# Proximity_Sensor.net
KiCad netlist of a schematic drawn in EAGLE
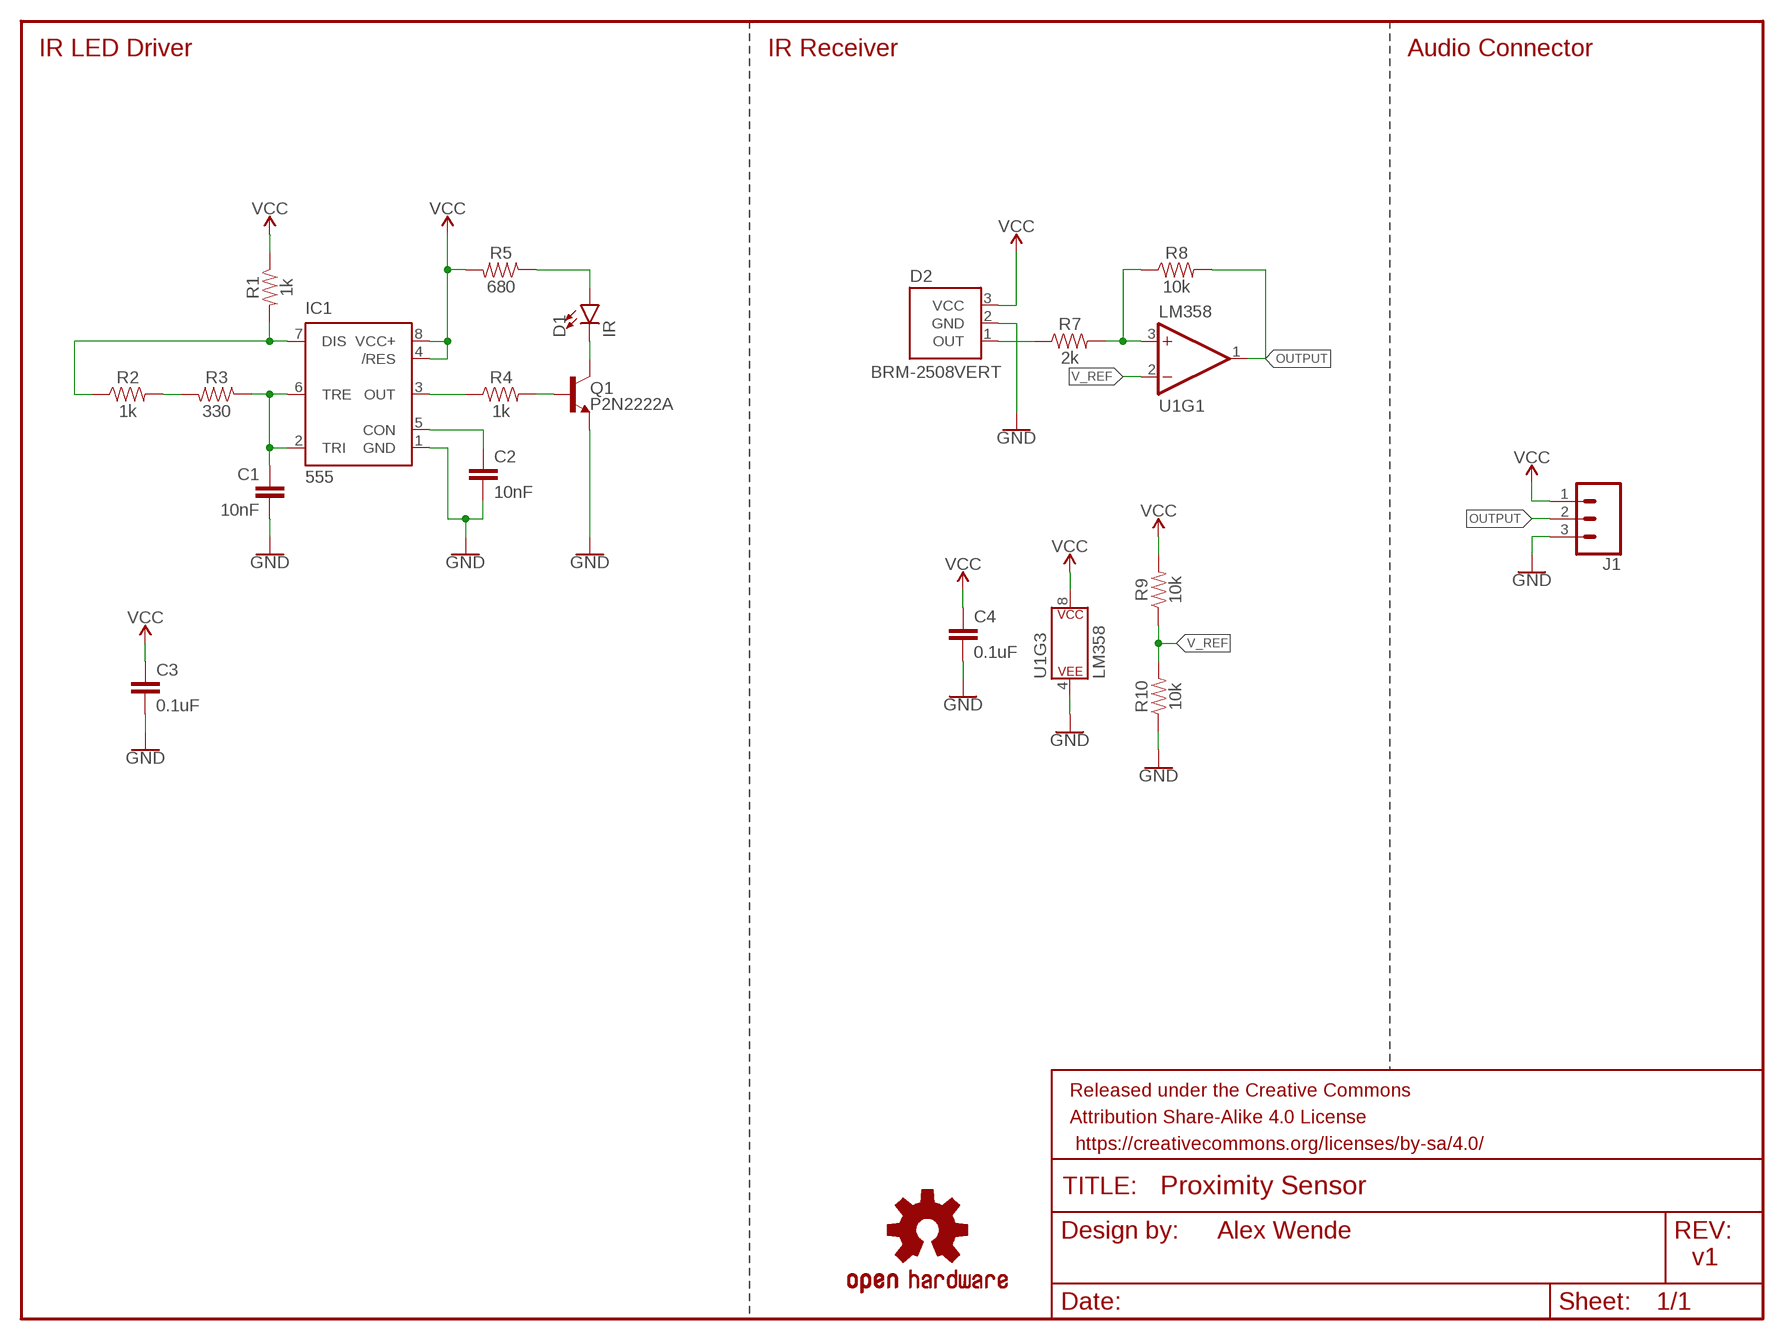
[diagram p0: schematic, sheet 1]

(export (version "E")
  (design (tool "Eeschema 10.0.6"))
  (components
    (comp (ref "C1")
      (value "10nF")
      (footprint "eagle-import:CAP-PTH-10MM")
      (libsource (lib "eagle-import") (part "10NF-PTH-10MM-10000V-1-%"))
    )
    (comp (ref "C2")
      (value "10nF")
      (footprint "eagle-import:CAP-PTH-10MM")
      (libsource (lib "eagle-import") (part "10NF-PTH-10MM-10000V-1-%"))
    )
    (comp (ref "C3")
      (value "0.1uF")
      (footprint "eagle-import:CAP-PTH-SMALL-KIT")
      (libsource (lib "eagle-import") (part "0.1UF-KIT-EZ-50V-20%"))
    )
    (comp (ref "C4")
      (value "0.1uF")
      (footprint "eagle-import:CAP-PTH-SMALL-KIT")
      (libsource (lib "eagle-import") (part "0.1UF-KIT-EZ-50V-20%"))
    )
    (comp (ref "D1")
      (value "IR")
      (footprint "eagle-import:LED_5MM-KIT")
      (libsource (lib "eagle-import") (part "LED5MM-KIT"))
    )
    (comp (ref "D2")
      (value "BRM-2508VERT")
      (footprint "eagle-import:BRM-2508_VERT")
      (libsource (lib "eagle-import") (part "BRM-2508VERT"))
    )
    (comp (ref "FRAME1")
      (value "FRAME-LETTERNO_PACKAGE")
      (footprint "eagle-import:DUMMY")
      (fields (field (name "DESIGNER") "Nobody"))
      (libsource (lib "eagle-import") (part "FRAME-LETTERNO_PACKAGE"))
    )
    (comp (ref "IC1")
      (value "555")
      (footprint "eagle-import:DIP08-KIT")
      (libsource (lib "eagle-import") (part "555KIT"))
    )
    (comp (ref "J1")
      (value "CONN_03LONGPADS")
      (footprint "eagle-import:1X03_LONGPADS")
      (libsource (lib "eagle-import") (part "CONN_03LONGPADS"))
    )
    (comp (ref "LOGO1")
      (value "OSHW-LOGOM")
      (footprint "eagle-import:OSHW-LOGO-M")
      (libsource (lib "eagle-import") (part "OSHW-LOGOM"))
    )
    (comp (ref "Q1")
      (value "P2N2222A")
      (footprint "eagle-import:TO-92")
      (libsource (lib "eagle-import") (part "TRANS_NPN-P2N2222A"))
    )
    (comp (ref "R1")
      (value "1k")
      (footprint "eagle-import:AXIAL-0.3-KIT")
      (libsource (lib "eagle-import") (part "1KOHM-HORIZ_KIT-1/4W-1%"))
    )
    (comp (ref "R2")
      (value "1k")
      (footprint "eagle-import:AXIAL-0.3-KIT")
      (libsource (lib "eagle-import") (part "1KOHM-HORIZ_KIT-1/4W-1%"))
    )
    (comp (ref "R3")
      (value "330")
      (footprint "eagle-import:AXIAL-0.3-KIT")
      (libsource (lib "eagle-import") (part "1KOHM-HORIZ_KIT-1/4W-1%"))
    )
    (comp (ref "R4")
      (value "1k")
      (footprint "eagle-import:AXIAL-0.3-KIT")
      (libsource (lib "eagle-import") (part "1KOHM-HORIZ_KIT-1/4W-1%"))
    )
    (comp (ref "R5")
      (value "680")
      (footprint "eagle-import:AXIAL-0.3-KIT")
      (libsource (lib "eagle-import") (part "1KOHM-HORIZ_KIT-1/4W-1%"))
    )
    (comp (ref "R7")
      (value "2k")
      (footprint "eagle-import:AXIAL-0.3-KIT")
      (libsource (lib "eagle-import") (part "1KOHM-HORIZ_KIT-1/4W-1%"))
    )
    (comp (ref "R8")
      (value "10k")
      (footprint "eagle-import:AXIAL-0.3-KIT")
      (libsource (lib "eagle-import") (part "1KOHM-HORIZ_KIT-1/4W-1%"))
    )
    (comp (ref "R9")
      (value "10k")
      (footprint "eagle-import:AXIAL-0.3-KIT")
      (libsource (lib "eagle-import") (part "1KOHM-HORIZ_KIT-1/4W-1%"))
    )
    (comp (ref "R10")
      (value "10k")
      (footprint "eagle-import:AXIAL-0.3-KIT")
      (libsource (lib "eagle-import") (part "1KOHM-HORIZ_KIT-1/4W-1%"))
    )
    (comp (ref "U1")
      (value "LM358")
      (footprint "eagle-import:DIP08-KIT")
      (libsource (lib "eagle-import") (part "LM358KIT"))
    )
  )
  (nets
    (net (code "1") (name "GND") (class "Default")
      (node (ref "C1") (pin "2") (pinfunction "2_2") (pintype "passive"))
      (node (ref "C2") (pin "2") (pinfunction "2_2") (pintype "passive"))
      (node (ref "C3") (pin "2") (pinfunction "2_2") (pintype "passive"))
      (node (ref "C4") (pin "2") (pinfunction "2_2") (pintype "passive"))
      (node (ref "D2") (pin "2") (pinfunction "GND_2") (pintype "bidirectional"))
      (node (ref "IC1") (pin "1") (pinfunction "GND_1") (pintype "power_in"))
      (node (ref "J1") (pin "3") (pinfunction "3_3") (pintype "passive"))
      (node (ref "Q1") (pin "3") (pinfunction "E_3") (pintype "passive"))
      (node (ref "R10") (pin "P$1") (pinfunction "1_P$1") (pintype "passive"))
      (node (ref "U1") (pin "4") (pinfunction "P$V-_4") (pintype "bidirectional"))
    )
    (net (code "2") (name "Net-(D1-C)") (class "Default")
      (node (ref "D1") (pin "K") (pinfunction "C_K") (pintype "passive"))
      (node (ref "Q1") (pin "1") (pinfunction "C_1") (pintype "passive"))
    )
    (net (code "3") (name "Net-(D2-OUT)") (class "Default")
      (node (ref "D2") (pin "1") (pinfunction "OUT_1") (pintype "bidirectional"))
      (node (ref "R7") (pin "P$1") (pinfunction "1_P$1") (pintype "passive"))
    )
    (net (code "4") (name "Net-(IC1-CON)") (class "Default")
      (node (ref "C2") (pin "1") (pinfunction "1_1") (pintype "passive"))
      (node (ref "IC1") (pin "5") (pinfunction "CON_5") (pintype "input"))
    )
    (net (code "5") (name "Net-(IC1-DIS)") (class "Default")
      (node (ref "IC1") (pin "7") (pinfunction "DIS_7") (pintype "input"))
      (node (ref "R1") (pin "P$2") (pinfunction "2_P$2") (pintype "passive"))
      (node (ref "R2") (pin "P$1") (pinfunction "1_P$1") (pintype "passive"))
    )
    (net (code "6") (name "Net-(IC1-OUT)") (class "Default")
      (node (ref "IC1") (pin "3") (pinfunction "OUT_3") (pintype "output"))
      (node (ref "R4") (pin "P$1") (pinfunction "1_P$1") (pintype "passive"))
    )
    (net (code "7") (name "Net-(IC1-TRE)") (class "Default")
      (node (ref "C1") (pin "1") (pinfunction "1_1") (pintype "passive"))
      (node (ref "IC1") (pin "2") (pinfunction "TRI_2") (pintype "input"))
      (node (ref "IC1") (pin "6") (pinfunction "TRE_6") (pintype "input"))
      (node (ref "R3") (pin "P$1") (pinfunction "1_P$1") (pintype "passive"))
    )
    (net (code "8") (name "Net-(Q1-B)") (class "Default")
      (node (ref "Q1") (pin "2") (pinfunction "B_2") (pintype "passive"))
      (node (ref "R4") (pin "P$2") (pinfunction "2_P$2") (pintype "passive"))
    )
    (net (code "9") (name "Net-(R2-2)") (class "Default")
      (node (ref "R2") (pin "P$2") (pinfunction "2_P$2") (pintype "passive"))
      (node (ref "R3") (pin "P$2") (pinfunction "2_P$2") (pintype "passive"))
    )
    (net (code "10") (name "Net-(R5-1)") (class "Default")
      (node (ref "D1") (pin "A") (pinfunction "A_A") (pintype "passive"))
      (node (ref "R5") (pin "P$1") (pinfunction "1_P$1") (pintype "passive"))
    )
    (net (code "11") (name "Net-(R7-2)") (class "Default")
      (node (ref "R7") (pin "P$2") (pinfunction "2_P$2") (pintype "passive"))
      (node (ref "R8") (pin "P$1") (pinfunction "1_P$1") (pintype "passive"))
      (node (ref "U1") (pin "3") (pinfunction "+IN_3") (pintype "input"))
    )
    (net (code "12") (name "OUTPUT") (class "Default")
      (node (ref "J1") (pin "2") (pinfunction "2_2") (pintype "passive"))
      (node (ref "R8") (pin "P$2") (pinfunction "2_P$2") (pintype "passive"))
      (node (ref "U1") (pin "1") (pinfunction "OUT_1") (pintype "output"))
    )
    (net (code "13") (name "VCC") (class "Default")
      (node (ref "C3") (pin "1") (pinfunction "1_1") (pintype "passive"))
      (node (ref "C4") (pin "1") (pinfunction "1_1") (pintype "passive"))
      (node (ref "D2") (pin "3") (pinfunction "VCC_3") (pintype "bidirectional"))
      (node (ref "IC1") (pin "4") (pinfunction "/RES_4") (pintype "input"))
      (node (ref "IC1") (pin "8") (pinfunction "VCC+_8") (pintype "power_in"))
      (node (ref "J1") (pin "1") (pinfunction "1_1") (pintype "passive"))
      (node (ref "R1") (pin "P$1") (pinfunction "1_P$1") (pintype "passive"))
      (node (ref "R5") (pin "P$2") (pinfunction "2_P$2") (pintype "passive"))
      (node (ref "R9") (pin "P$2") (pinfunction "2_P$2") (pintype "passive"))
      (node (ref "U1") (pin "8") (pinfunction "P$V+_8") (pintype "bidirectional"))
    )
    (net (code "14") (name "V_REF") (class "Default")
      (node (ref "R10") (pin "P$2") (pinfunction "2_P$2") (pintype "passive"))
      (node (ref "R9") (pin "P$1") (pinfunction "1_P$1") (pintype "passive"))
      (node (ref "U1") (pin "2") (pinfunction "-IN_2") (pintype "input"))
    )
  )
)
